# MXM_3_1_Connector_Interface.net
KiCad netlist of a schematic drawn in Altium Designer
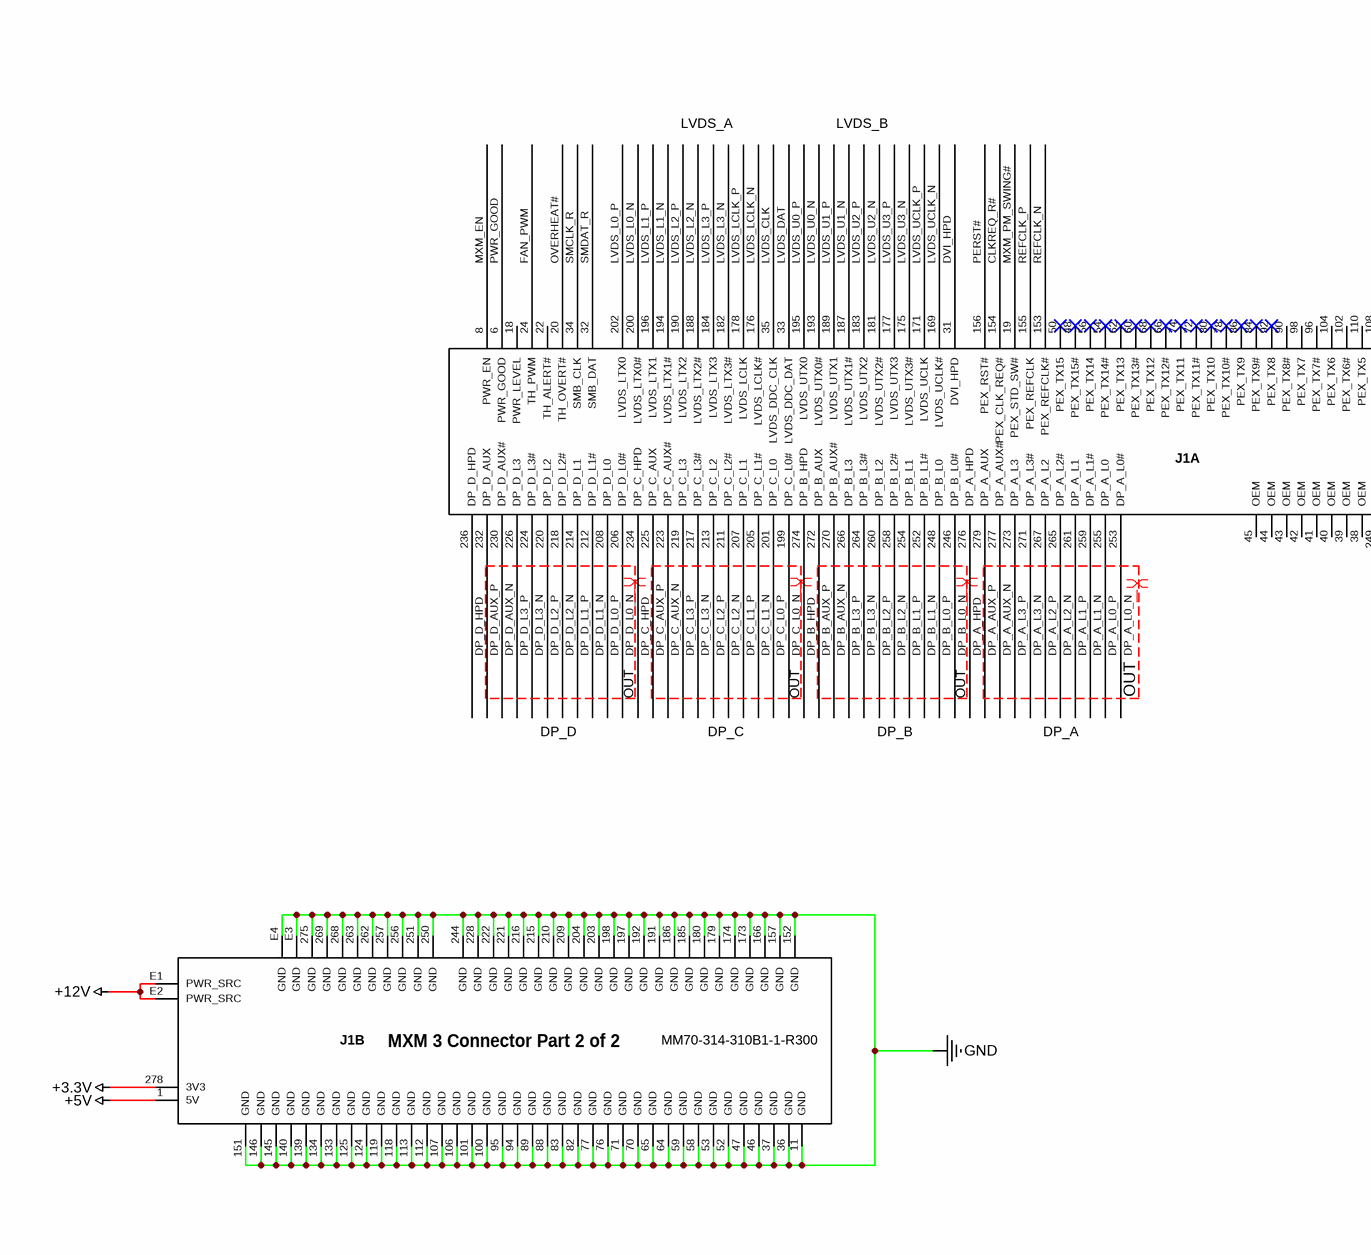
[diagram p0: MXM 3.1 Connector Interface.SchDoc, left]
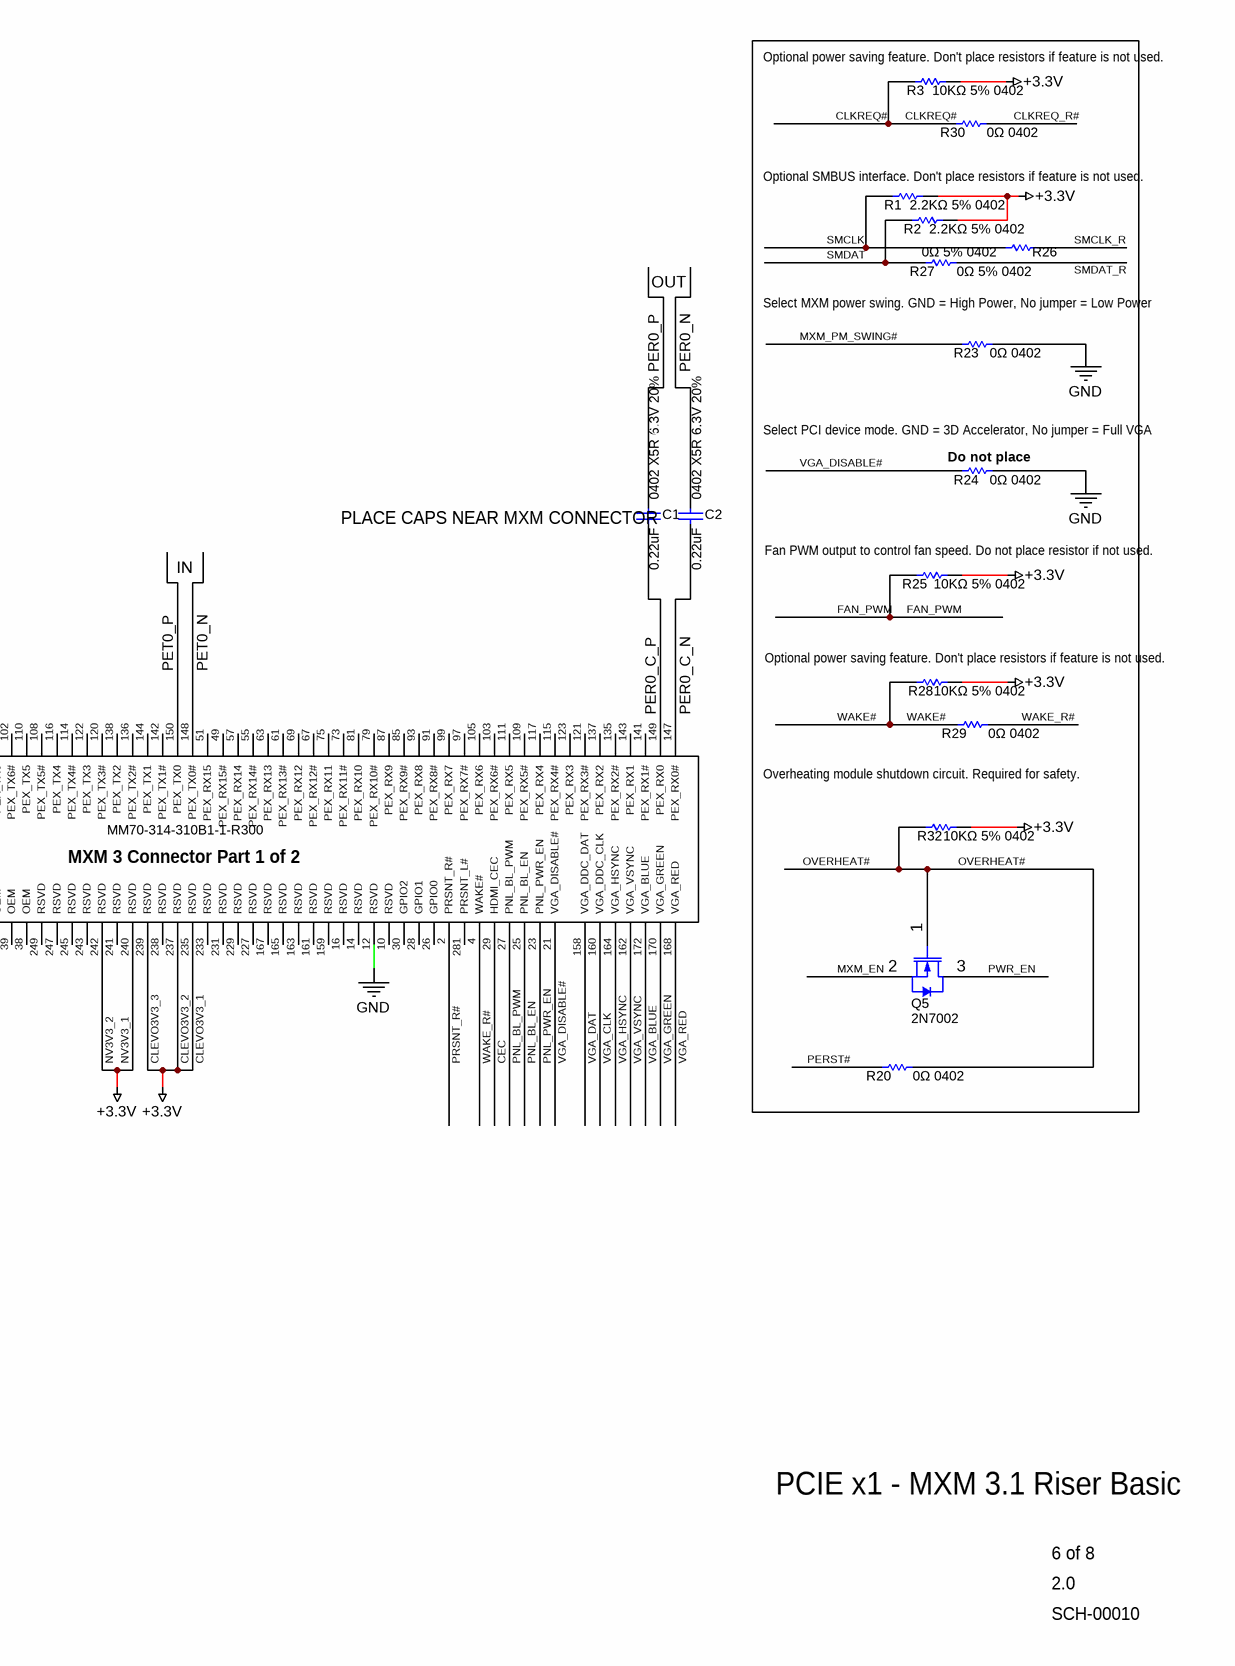
[diagram p1: MXM 3.1 Connector Interface.SchDoc, right]

(export (version "E")
  (design (tool "Eeschema 10.0.6"))
  (components
    (comp (ref "C1")
      (value "0.22uF       0402 X5R 6.3V 20%")
      (footprint "CAPC0603X33X15NL03T05")
      (fields (field (name "MANUFACTURER") "Samsung") (field (name "PART NUMBER") "CL03A224MQ3NNNC"))
      (libsource (lib "Altium Content Vault") (part "CAP"))
    )
    (comp (ref "C2")
      (value "0.22uF       0402 X5R 6.3V 20%")
      (footprint "CAPC0603X33X15NL03T05")
      (fields (field (name "MANUFACTURER") "Samsung") (field (name "PART NUMBER") "CL03A224MQ3NNNC"))
      (libsource (lib "Altium Content Vault") (part "CAP"))
    )
    (comp (ref "J1")
      (value "MM70-314-310B1-1-R300")
      (footprint "JAE_MM70-314-310B1-2-R300")
      (description "314 Position Female Connector MXM 3.0 Gold 0.020 _0.50mm_ Black")
      (fields (field (name "MF") "JAE Electronics") (field (name "DIGI-KEY_PART_NUMBER") "670-2431-1-ND"))
      (libsource (lib "MM70-314-310B1-1-R300") (part "MM70-314-310B1-1-R300"))
    )
    (comp (ref "Q5")
      (value "2N7002")
      (footprint "INF-PG-SOT23_M")
      (fields (field (name "MANUFACTURER") "Infineon"))
      (libsource (lib "Altium Content Vault") (part "INF-NDMOS-GSD-3"))
    )
    (comp (ref "R1")
      (value "2.2KΩ 5% 0402")
      (footprint "RESC0201(0603)_L")
      (description "1M 0.05W 1% 0201 (0603 Metric)  SMD")
      (fields (field (name "TOLERANCE") "1 %") (field (name "POWER") "0.05 W"))
      (libsource (lib "Altium Content Vault") (part "RES"))
    )
    (comp (ref "R2")
      (value "2.2KΩ 5% 0402")
      (footprint "RESC0201(0603)_L")
      (description "1M 0.05W 1% 0201 (0603 Metric)  SMD")
      (fields (field (name "TOLERANCE") "1 %") (field (name "POWER") "0.05 W"))
      (libsource (lib "Altium Content Vault") (part "RES"))
    )
    (comp (ref "R3")
      (value "10KΩ 5% 0402")
      (footprint "RESC0201(0603)_L")
      (description "1M 0.05W 1% 0201 (0603 Metric)  SMD")
      (fields (field (name "TOLERANCE") "1 %") (field (name "POWER") "0.05 W"))
      (libsource (lib "Altium Content Vault") (part "RES"))
    )
    (comp (ref "R20")
      (value "0Ω 0402")
      (footprint "RESC0201(0603)_L")
      (description "1M 0.05W 1% 0201 (0603 Metric)  SMD")
      (fields (field (name "TOLERANCE") "1 %") (field (name "POWER") "0.05 W"))
      (libsource (lib "Altium Content Vault") (part "RES"))
    )
    (comp (ref "R23")
      (value "0Ω 0402")
      (footprint "RESC0201(0603)_L")
      (description "1M 0.05W 1% 0201 (0603 Metric)  SMD")
      (fields (field (name "TOLERANCE") "1 %") (field (name "POWER") "0.05 W"))
      (libsource (lib "Altium Content Vault") (part "RES"))
    )
    (comp (ref "R24")
      (value "0Ω 0402")
      (footprint "RESC0201(0603)_L")
      (description "1M 0.05W 1% 0201 (0603 Metric)  SMD")
      (fields (field (name "TOLERANCE") "1 %") (field (name "POWER") "0.05 W"))
      (libsource (lib "Altium Content Vault") (part "RES"))
    )
    (comp (ref "R25")
      (value "10KΩ 5% 0402")
      (footprint "RESC0201(0603)_L")
      (description "1M 0.05W 1% 0201 (0603 Metric)  SMD")
      (fields (field (name "TOLERANCE") "1 %") (field (name "POWER") "0.05 W"))
      (libsource (lib "Altium Content Vault") (part "RES"))
    )
    (comp (ref "R26")
      (value "0Ω 5% 0402")
      (footprint "RESC0201(0603)_L")
      (description "1M 0.05W 1% 0201 (0603 Metric)  SMD")
      (fields (field (name "TOLERANCE") "1 %") (field (name "POWER") "0.05 W"))
      (libsource (lib "Altium Content Vault") (part "RES"))
    )
    (comp (ref "R27")
      (value "0Ω 5% 0402")
      (footprint "RESC0201(0603)_L")
      (description "1M 0.05W 1% 0201 (0603 Metric)  SMD")
      (fields (field (name "TOLERANCE") "1 %") (field (name "POWER") "0.05 W"))
      (libsource (lib "Altium Content Vault") (part "RES"))
    )
    (comp (ref "R28")
      (value "10KΩ 5% 0402")
      (footprint "RESC0201(0603)_L")
      (description "1M 0.05W 1% 0201 (0603 Metric)  SMD")
      (fields (field (name "TOLERANCE") "1 %") (field (name "POWER") "0.05 W"))
      (libsource (lib "Altium Content Vault") (part "RES"))
    )
    (comp (ref "R29")
      (value "0Ω 0402")
      (footprint "RESC0201(0603)_L")
      (description "1M 0.05W 1% 0201 (0603 Metric)  SMD")
      (fields (field (name "TOLERANCE") "1 %") (field (name "POWER") "0.05 W"))
      (libsource (lib "Altium Content Vault") (part "RES"))
    )
    (comp (ref "R30")
      (value "0Ω 0402")
      (footprint "RESC0201(0603)_L")
      (description "1M 0.05W 1% 0201 (0603 Metric)  SMD")
      (fields (field (name "TOLERANCE") "1 %") (field (name "POWER") "0.05 W"))
      (libsource (lib "Altium Content Vault") (part "RES"))
    )
    (comp (ref "R32")
      (value "10KΩ 5% 0402")
      (footprint "RESC0201(0603)_L")
      (description "1M 0.05W 1% 0201 (0603 Metric)  SMD")
      (fields (field (name "TOLERANCE") "1 %") (field (name "POWER") "0.05 W"))
      (libsource (lib "Altium Content Vault") (part "RES"))
    )
  )
  (nets
    (net (code "1") (name "+3.3V") (class "Default")
      (node (ref "J1") (pin "235") (pinfunction "RSVD_235") (pintype "passive"))
      (node (ref "J1") (pin "237") (pinfunction "RSVD_237") (pintype "passive"))
      (node (ref "J1") (pin "239") (pinfunction "RSVD_239") (pintype "passive"))
      (node (ref "J1") (pin "240") (pinfunction "RSVD_240") (pintype "passive"))
      (node (ref "J1") (pin "242") (pinfunction "RSVD_242") (pintype "passive"))
      (node (ref "J1") (pin "278") (pinfunction "3V3_278") (pintype "passive"))
      (node (ref "R1") (pin "1") (pinfunction "1_1") (pintype "passive"))
      (node (ref "R2") (pin "1") (pinfunction "1_1") (pintype "passive"))
      (node (ref "R25") (pin "1") (pinfunction "1_1") (pintype "passive"))
      (node (ref "R28") (pin "1") (pinfunction "1_1") (pintype "passive"))
      (node (ref "R3") (pin "1") (pinfunction "1_1") (pintype "passive"))
      (node (ref "R32") (pin "1") (pinfunction "1_1") (pintype "passive"))
    )
    (net (code "2") (name "+5V") (class "Default")
      (node (ref "J1") (pin "1") (pinfunction "5V_1") (pintype "passive"))
    )
    (net (code "3") (name "+12V") (class "Default")
      (node (ref "J1") (pin "E1") (pinfunction "PWR_SRC_E1") (pintype "passive"))
      (node (ref "J1") (pin "E2") (pinfunction "PWR_SRC_E2") (pintype "passive"))
    )
    (net (code "4") (name "/CEC") (class "Default")
      (node (ref "J1") (pin "29") (pinfunction "HDMI_CEC_29") (pintype "passive"))
    )
    (net (code "5") (name "/CLKREQ#") (class "Default")
      (node (ref "R3") (pin "2") (pinfunction "2_2") (pintype "passive"))
      (node (ref "R30") (pin "2") (pinfunction "2_2") (pintype "passive"))
    )
    (net (code "6") (name "/CLKREQ_R#") (class "Default")
      (node (ref "J1") (pin "154") (pinfunction "PEX_CLK_REQ#_154") (pintype "passive"))
      (node (ref "R30") (pin "1") (pinfunction "1_1") (pintype "passive"))
    )
    (net (code "7") (name "/DP_A_AUX_N") (class "Default")
      (node (ref "J1") (pin "277") (pinfunction "DP_A_AUX#_277") (pintype "passive"))
    )
    (net (code "8") (name "/DP_A_AUX_P") (class "Default")
      (node (ref "J1") (pin "279") (pinfunction "DP_A_AUX_279") (pintype "passive"))
    )
    (net (code "9") (name "/DP_A_HPD") (class "Default")
      (node (ref "J1") (pin "276") (pinfunction "DP_A_HPD_276") (pintype "passive"))
    )
    (net (code "10") (name "/DP_A_L0_N") (class "Default")
      (node (ref "J1") (pin "253") (pinfunction "DP_A_L0#_253") (pintype "passive"))
    )
    (net (code "11") (name "/DP_A_L0_P") (class "Default")
      (node (ref "J1") (pin "255") (pinfunction "DP_A_L0_255") (pintype "passive"))
    )
    (net (code "12") (name "/DP_A_L1_N") (class "Default")
      (node (ref "J1") (pin "259") (pinfunction "DP_A_L1#_259") (pintype "passive"))
    )
    (net (code "13") (name "/DP_A_L1_P") (class "Default")
      (node (ref "J1") (pin "261") (pinfunction "DP_A_L1_261") (pintype "passive"))
    )
    (net (code "14") (name "/DP_A_L2_N") (class "Default")
      (node (ref "J1") (pin "265") (pinfunction "DP_A_L2#_265") (pintype "passive"))
    )
    (net (code "15") (name "/DP_A_L2_P") (class "Default")
      (node (ref "J1") (pin "267") (pinfunction "DP_A_L2_267") (pintype "passive"))
    )
    (net (code "16") (name "/DP_A_L3_N") (class "Default")
      (node (ref "J1") (pin "271") (pinfunction "DP_A_L3#_271") (pintype "passive"))
    )
    (net (code "17") (name "/DP_A_L3_P") (class "Default")
      (node (ref "J1") (pin "273") (pinfunction "DP_A_L3_273") (pintype "passive"))
    )
    (net (code "18") (name "/DP_B_AUX_N") (class "Default")
      (node (ref "J1") (pin "270") (pinfunction "DP_B_AUX#_270") (pintype "passive"))
    )
    (net (code "19") (name "/DP_B_AUX_P") (class "Default")
      (node (ref "J1") (pin "272") (pinfunction "DP_B_AUX_272") (pintype "passive"))
    )
    (net (code "20") (name "/DP_B_HPD") (class "Default")
      (node (ref "J1") (pin "274") (pinfunction "DP_B_HPD_274") (pintype "passive"))
    )
    (net (code "21") (name "/DP_B_L0_N") (class "Default")
      (node (ref "J1") (pin "246") (pinfunction "DP_B_L0#_246") (pintype "passive"))
    )
    (net (code "22") (name "/DP_B_L0_P") (class "Default")
      (node (ref "J1") (pin "248") (pinfunction "DP_B_L0_248") (pintype "passive"))
    )
    (net (code "23") (name "/DP_B_L1_N") (class "Default")
      (node (ref "J1") (pin "252") (pinfunction "DP_B_L1#_252") (pintype "passive"))
    )
    (net (code "24") (name "/DP_B_L1_P") (class "Default")
      (node (ref "J1") (pin "254") (pinfunction "DP_B_L1_254") (pintype "passive"))
    )
    (net (code "25") (name "/DP_B_L2_N") (class "Default")
      (node (ref "J1") (pin "258") (pinfunction "DP_B_L2#_258") (pintype "passive"))
    )
    (net (code "26") (name "/DP_B_L2_P") (class "Default")
      (node (ref "J1") (pin "260") (pinfunction "DP_B_L2_260") (pintype "passive"))
    )
    (net (code "27") (name "/DP_B_L3_N") (class "Default")
      (node (ref "J1") (pin "264") (pinfunction "DP_B_L3#_264") (pintype "passive"))
    )
    (net (code "28") (name "/DP_B_L3_P") (class "Default")
      (node (ref "J1") (pin "266") (pinfunction "DP_B_L3_266") (pintype "passive"))
    )
    (net (code "29") (name "/DP_C_AUX_N") (class "Default")
      (node (ref "J1") (pin "223") (pinfunction "DP_C_AUX#_223") (pintype "passive"))
    )
    (net (code "30") (name "/DP_C_AUX_P") (class "Default")
      (node (ref "J1") (pin "225") (pinfunction "DP_C_AUX_225") (pintype "passive"))
    )
    (net (code "31") (name "/DP_C_HPD") (class "Default")
      (node (ref "J1") (pin "234") (pinfunction "DP_C_HPD_234") (pintype "passive"))
    )
    (net (code "32") (name "/DP_C_L0_N") (class "Default")
      (node (ref "J1") (pin "199") (pinfunction "DP_C_L0#_199") (pintype "passive"))
    )
    (net (code "33") (name "/DP_C_L0_P") (class "Default")
      (node (ref "J1") (pin "201") (pinfunction "DP_C_L0_201") (pintype "passive"))
    )
    (net (code "34") (name "/DP_C_L1_N") (class "Default")
      (node (ref "J1") (pin "205") (pinfunction "DP_C_L1#_205") (pintype "passive"))
    )
    (net (code "35") (name "/DP_C_L1_P") (class "Default")
      (node (ref "J1") (pin "207") (pinfunction "DP_C_L1_207") (pintype "passive"))
    )
    (net (code "36") (name "/DP_C_L2_N") (class "Default")
      (node (ref "J1") (pin "211") (pinfunction "DP_C_L2#_211") (pintype "passive"))
    )
    (net (code "37") (name "/DP_C_L2_P") (class "Default")
      (node (ref "J1") (pin "213") (pinfunction "DP_C_L2_213") (pintype "passive"))
    )
    (net (code "38") (name "/DP_C_L3_N") (class "Default")
      (node (ref "J1") (pin "217") (pinfunction "DP_C_L3#_217") (pintype "passive"))
    )
    (net (code "39") (name "/DP_C_L3_P") (class "Default")
      (node (ref "J1") (pin "219") (pinfunction "DP_C_L3_219") (pintype "passive"))
    )
    (net (code "40") (name "/DP_D_AUX_N") (class "Default")
      (node (ref "J1") (pin "230") (pinfunction "DP_D_AUX#_230") (pintype "passive"))
    )
    (net (code "41") (name "/DP_D_AUX_P") (class "Default")
      (node (ref "J1") (pin "232") (pinfunction "DP_D_AUX_232") (pintype "passive"))
    )
    (net (code "42") (name "/DP_D_HPD") (class "Default")
      (node (ref "J1") (pin "236") (pinfunction "DP_D_HPD_236") (pintype "passive"))
    )
    (net (code "43") (name "/DP_D_L0_N") (class "Default")
      (node (ref "J1") (pin "206") (pinfunction "DP_D_L0#_206") (pintype "passive"))
    )
    (net (code "44") (name "/DP_D_L0_P") (class "Default")
      (node (ref "J1") (pin "208") (pinfunction "DP_D_L0_208") (pintype "passive"))
    )
    (net (code "45") (name "/DP_D_L1_N") (class "Default")
      (node (ref "J1") (pin "212") (pinfunction "DP_D_L1#_212") (pintype "passive"))
    )
    (net (code "46") (name "/DP_D_L1_P") (class "Default")
      (node (ref "J1") (pin "214") (pinfunction "DP_D_L1_214") (pintype "passive"))
    )
    (net (code "47") (name "/DP_D_L2_N") (class "Default")
      (node (ref "J1") (pin "218") (pinfunction "DP_D_L2#_218") (pintype "passive"))
    )
    (net (code "48") (name "/DP_D_L2_P") (class "Default")
      (node (ref "J1") (pin "220") (pinfunction "DP_D_L2_220") (pintype "passive"))
    )
    (net (code "49") (name "/DP_D_L3_N") (class "Default")
      (node (ref "J1") (pin "224") (pinfunction "DP_D_L3#_224") (pintype "passive"))
    )
    (net (code "50") (name "/DP_D_L3_P") (class "Default")
      (node (ref "J1") (pin "226") (pinfunction "DP_D_L3_226") (pintype "passive"))
    )
    (net (code "51") (name "/DVI_HPD") (class "Default")
      (node (ref "J1") (pin "31") (pinfunction "DVI_HPD_31") (pintype "passive"))
    )
    (net (code "52") (name "/FAN_PWM") (class "Default")
      (node (ref "J1") (pin "24") (pinfunction "TH_PWM_24") (pintype "passive"))
      (node (ref "R25") (pin "2") (pinfunction "2_2") (pintype "passive"))
    )
    (net (code "53") (name "/LVDS_CLK") (class "Default")
      (node (ref "J1") (pin "35") (pinfunction "LVDS_DDC_CLK_35") (pintype "passive"))
    )
    (net (code "54") (name "/LVDS_DAT") (class "Default")
      (node (ref "J1") (pin "33") (pinfunction "LVDS_DDC_DAT_33") (pintype "passive"))
    )
    (net (code "55") (name "/LVDS_L0_N") (class "Default")
      (node (ref "J1") (pin "200") (pinfunction "LVDS_LTX0#_200") (pintype "passive"))
    )
    (net (code "56") (name "/LVDS_L0_P") (class "Default")
      (node (ref "J1") (pin "202") (pinfunction "LVDS_LTX0_202") (pintype "passive"))
    )
    (net (code "57") (name "/LVDS_L1_N") (class "Default")
      (node (ref "J1") (pin "194") (pinfunction "LVDS_LTX1#_194") (pintype "passive"))
    )
    (net (code "58") (name "/LVDS_L1_P") (class "Default")
      (node (ref "J1") (pin "196") (pinfunction "LVDS_LTX1_196") (pintype "passive"))
    )
    (net (code "59") (name "/LVDS_L2_N") (class "Default")
      (node (ref "J1") (pin "188") (pinfunction "LVDS_LTX2#_188") (pintype "passive"))
    )
    (net (code "60") (name "/LVDS_L2_P") (class "Default")
      (node (ref "J1") (pin "190") (pinfunction "LVDS_LTX2_190") (pintype "passive"))
    )
    (net (code "61") (name "/LVDS_L3_N") (class "Default")
      (node (ref "J1") (pin "182") (pinfunction "LVDS_LTX3#_182") (pintype "passive"))
    )
    (net (code "62") (name "/LVDS_L3_P") (class "Default")
      (node (ref "J1") (pin "184") (pinfunction "LVDS_LTX3_184") (pintype "passive"))
    )
    (net (code "63") (name "/LVDS_LCLK_N") (class "Default")
      (node (ref "J1") (pin "176") (pinfunction "LVDS_LCLK#_176") (pintype "passive"))
    )
    (net (code "64") (name "/LVDS_LCLK_P") (class "Default")
      (node (ref "J1") (pin "178") (pinfunction "LVDS_LCLK_178") (pintype "passive"))
    )
    (net (code "65") (name "/LVDS_U0_N") (class "Default")
      (node (ref "J1") (pin "193") (pinfunction "LVDS_UTX0#_193") (pintype "passive"))
    )
    (net (code "66") (name "/LVDS_U0_P") (class "Default")
      (node (ref "J1") (pin "195") (pinfunction "LVDS_UTX0_195") (pintype "passive"))
    )
    (net (code "67") (name "/LVDS_U1_N") (class "Default")
      (node (ref "J1") (pin "187") (pinfunction "LVDS_UTX1#_187") (pintype "passive"))
    )
    (net (code "68") (name "/LVDS_U1_P") (class "Default")
      (node (ref "J1") (pin "189") (pinfunction "LVDS_UTX1_189") (pintype "passive"))
    )
    (net (code "69") (name "/LVDS_U2_N") (class "Default")
      (node (ref "J1") (pin "181") (pinfunction "LVDS_UTX2#_181") (pintype "passive"))
    )
    (net (code "70") (name "/LVDS_U2_P") (class "Default")
      (node (ref "J1") (pin "183") (pinfunction "LVDS_UTX2_183") (pintype "passive"))
    )
    (net (code "71") (name "/LVDS_U3_N") (class "Default")
      (node (ref "J1") (pin "175") (pinfunction "LVDS_UTX3#_175") (pintype "passive"))
    )
    (net (code "72") (name "/LVDS_U3_P") (class "Default")
      (node (ref "J1") (pin "177") (pinfunction "LVDS_UTX3_177") (pintype "passive"))
    )
    (net (code "73") (name "/LVDS_UCLK_N") (class "Default")
      (node (ref "J1") (pin "169") (pinfunction "LVDS_UCLK#_169") (pintype "passive"))
    )
    (net (code "74") (name "/LVDS_UCLK_P") (class "Default")
      (node (ref "J1") (pin "171") (pinfunction "LVDS_UCLK_171") (pintype "passive"))
    )
    (net (code "75") (name "/MXM_EN") (class "Default")
      (node (ref "J1") (pin "8") (pinfunction "PWR_EN_8") (pintype "passive"))
      (node (ref "Q5") (pin "2") (pinfunction "SOURCE_2") (pintype "passive"))
    )
    (net (code "76") (name "/MXM_PM_SWING#") (class "Default")
      (node (ref "J1") (pin "19") (pinfunction "PEX_STD_SW#_19") (pintype "passive"))
      (node (ref "R23") (pin "2") (pinfunction "2_2") (pintype "passive"))
    )
    (net (code "77") (name "/OVERHEAT#") (class "Default")
      (node (ref "J1") (pin "20") (pinfunction "TH_OVERT#_20") (pintype "passive"))
      (node (ref "Q5") (pin "1") (pinfunction "GATE_1") (pintype "passive"))
      (node (ref "R20") (pin "1") (pinfunction "1_1") (pintype "passive"))
      (node (ref "R32") (pin "2") (pinfunction "2_2") (pintype "passive"))
    )
    (net (code "78") (name "/PER0_C_N") (class "Default")
      (node (ref "C2") (pin "1") (pinfunction "1_1") (pintype "passive"))
      (node (ref "J1") (pin "147") (pinfunction "PEX_RX0#_147") (pintype "passive"))
    )
    (net (code "79") (name "/PER0_C_P") (class "Default")
      (node (ref "C1") (pin "1") (pinfunction "1_1") (pintype "passive"))
      (node (ref "J1") (pin "149") (pinfunction "PEX_RX0_149") (pintype "passive"))
    )
    (net (code "80") (name "/PER0_N") (class "Default")
      (node (ref "C2") (pin "2") (pinfunction "2_2") (pintype "passive"))
    )
    (net (code "81") (name "/PER0_P") (class "Default")
      (node (ref "C1") (pin "2") (pinfunction "2_2") (pintype "passive"))
    )
    (net (code "82") (name "/PERST#") (class "Default")
      (node (ref "J1") (pin "156") (pinfunction "PEX_RST#_156") (pintype "passive"))
      (node (ref "R20") (pin "2") (pinfunction "2_2") (pintype "passive"))
    )
    (net (code "83") (name "/PET0_N") (class "Default")
      (node (ref "J1") (pin "148") (pinfunction "PEX_TX0#_148") (pintype "passive"))
    )
    (net (code "84") (name "/PET0_P") (class "Default")
      (node (ref "J1") (pin "150") (pinfunction "PEX_TX0_150") (pintype "passive"))
    )
    (net (code "85") (name "/PNL_BL_EN") (class "Default")
      (node (ref "J1") (pin "25") (pinfunction "PNL_BL_EN_25") (pintype "passive"))
    )
    (net (code "86") (name "/PNL_BL_PWM") (class "Default")
      (node (ref "J1") (pin "27") (pinfunction "PNL_BL_PWM_27") (pintype "passive"))
    )
    (net (code "87") (name "/PNL_PWR_EN") (class "Default")
      (node (ref "J1") (pin "23") (pinfunction "PNL_PWR_EN_23") (pintype "passive"))
    )
    (net (code "88") (name "/PRSNT_R#") (class "Default")
      (node (ref "J1") (pin "2") (pinfunction "PRSNT_R#_2") (pintype "passive"))
    )
    (net (code "89") (name "/PWR_EN") (class "Default")
      (node (ref "Q5") (pin "3") (pinfunction "DRAIN_3") (pintype "passive"))
    )
    (net (code "90") (name "/PWR_GOOD") (class "Default")
      (node (ref "J1") (pin "6") (pinfunction "PWR_GOOD_6") (pintype "passive"))
    )
    (net (code "91") (name "/REFCLK_N") (class "Default")
      (node (ref "J1") (pin "153") (pinfunction "PEX_REFCLK#_153") (pintype "passive"))
    )
    (net (code "92") (name "/REFCLK_P") (class "Default")
      (node (ref "J1") (pin "155") (pinfunction "PEX_REFCLK_155") (pintype "passive"))
    )
    (net (code "93") (name "/SMCLK") (class "Default")
      (node (ref "R1") (pin "2") (pinfunction "2_2") (pintype "passive"))
      (node (ref "R26") (pin "2") (pinfunction "2_2") (pintype "passive"))
    )
    (net (code "94") (name "/SMCLK_R") (class "Default")
      (node (ref "J1") (pin "34") (pinfunction "SMB_CLK_34") (pintype "passive"))
      (node (ref "R26") (pin "1") (pinfunction "1_1") (pintype "passive"))
    )
    (net (code "95") (name "/SMDAT") (class "Default")
      (node (ref "R2") (pin "2") (pinfunction "2_2") (pintype "passive"))
      (node (ref "R27") (pin "2") (pinfunction "2_2") (pintype "passive"))
    )
    (net (code "96") (name "/SMDAT_R") (class "Default")
      (node (ref "J1") (pin "32") (pinfunction "SMB_DAT_32") (pintype "passive"))
      (node (ref "R27") (pin "1") (pinfunction "1_1") (pintype "passive"))
    )
    (net (code "97") (name "/VGA_BLUE") (class "Default")
      (node (ref "J1") (pin "172") (pinfunction "VGA_BLUE_172") (pintype "passive"))
    )
    (net (code "98") (name "/VGA_CLK") (class "Default")
      (node (ref "J1") (pin "160") (pinfunction "VGA_DDC_CLK_160") (pintype "passive"))
    )
    (net (code "99") (name "/VGA_DAT") (class "Default")
      (node (ref "J1") (pin "158") (pinfunction "VGA_DDC_DAT_158") (pintype "passive"))
    )
    (net (code "100") (name "/VGA_DISABLE#") (class "Default")
      (node (ref "J1") (pin "21") (pinfunction "VGA_DISABLE#_21") (pintype "passive"))
      (node (ref "R24") (pin "2") (pinfunction "2_2") (pintype "passive"))
    )
    (net (code "101") (name "/VGA_GREEN") (class "Default")
      (node (ref "J1") (pin "170") (pinfunction "VGA_GREEN_170") (pintype "passive"))
    )
    (net (code "102") (name "/VGA_HSYNC") (class "Default")
      (node (ref "J1") (pin "164") (pinfunction "VGA_HSYNC_164") (pintype "passive"))
    )
    (net (code "103") (name "/VGA_RED") (class "Default")
      (node (ref "J1") (pin "168") (pinfunction "VGA_RED_168") (pintype "passive"))
    )
    (net (code "104") (name "/VGA_VSYNC") (class "Default")
      (node (ref "J1") (pin "162") (pinfunction "VGA_VSYNC_162") (pintype "passive"))
    )
    (net (code "105") (name "/WAKE#") (class "Default")
      (node (ref "R28") (pin "2") (pinfunction "2_2") (pintype "passive"))
      (node (ref "R29") (pin "2") (pinfunction "2_2") (pintype "passive"))
    )
    (net (code "106") (name "/WAKE_R#") (class "Default")
      (node (ref "J1") (pin "4") (pinfunction "WAKE#_4") (pintype "passive"))
      (node (ref "R29") (pin "1") (pinfunction "1_1") (pintype "passive"))
    )
    (net (code "107") (name "GND") (class "Default")
      (node (ref "J1") (pin "100") (pinfunction "GND_100") (pintype "passive"))
      (node (ref "J1") (pin "101") (pinfunction "GND_101") (pintype "passive"))
      (node (ref "J1") (pin "106") (pinfunction "GND_106") (pintype "passive"))
      (node (ref "J1") (pin "107") (pinfunction "GND_107") (pintype "passive"))
      (node (ref "J1") (pin "11") (pinfunction "GND_11") (pintype "passive"))
      (node (ref "J1") (pin "112") (pinfunction "GND_112") (pintype "passive"))
      (node (ref "J1") (pin "113") (pinfunction "GND_113") (pintype "passive"))
      (node (ref "J1") (pin "118") (pinfunction "GND_118") (pintype "passive"))
      (node (ref "J1") (pin "119") (pinfunction "GND_119") (pintype "passive"))
      (node (ref "J1") (pin "12") (pinfunction "RSVD_12") (pintype "passive"))
      (node (ref "J1") (pin "124") (pinfunction "GND_124") (pintype "passive"))
      (node (ref "J1") (pin "125") (pinfunction "GND_125") (pintype "passive"))
      (node (ref "J1") (pin "133") (pinfunction "GND_133") (pintype "passive"))
      (node (ref "J1") (pin "134") (pinfunction "GND_134") (pintype "passive"))
      (node (ref "J1") (pin "139") (pinfunction "GND_139") (pintype "passive"))
      (node (ref "J1") (pin "140") (pinfunction "GND_140") (pintype "passive"))
      (node (ref "J1") (pin "145") (pinfunction "GND_145") (pintype "passive"))
      (node (ref "J1") (pin "146") (pinfunction "GND_146") (pintype "passive"))
      (node (ref "J1") (pin "151") (pinfunction "GND_151") (pintype "passive"))
      (node (ref "J1") (pin "152") (pinfunction "GND_152") (pintype "passive"))
      (node (ref "J1") (pin "157") (pinfunction "GND_157") (pintype "passive"))
      (node (ref "J1") (pin "166") (pinfunction "GND_166") (pintype "passive"))
      (node (ref "J1") (pin "173") (pinfunction "GND_173") (pintype "passive"))
      (node (ref "J1") (pin "174") (pinfunction "GND_174") (pintype "passive"))
      (node (ref "J1") (pin "179") (pinfunction "GND_179") (pintype "passive"))
      (node (ref "J1") (pin "180") (pinfunction "GND_180") (pintype "passive"))
      (node (ref "J1") (pin "185") (pinfunction "GND_185") (pintype "passive"))
      (node (ref "J1") (pin "186") (pinfunction "GND_186") (pintype "passive"))
      (node (ref "J1") (pin "191") (pinfunction "GND_191") (pintype "passive"))
      (node (ref "J1") (pin "192") (pinfunction "GND_192") (pintype "passive"))
      (node (ref "J1") (pin "197") (pinfunction "GND_197") (pintype "passive"))
      (node (ref "J1") (pin "198") (pinfunction "GND_198") (pintype "passive"))
      (node (ref "J1") (pin "203") (pinfunction "GND_203") (pintype "passive"))
      (node (ref "J1") (pin "204") (pinfunction "GND_204") (pintype "passive"))
      (node (ref "J1") (pin "209") (pinfunction "GND_209") (pintype "passive"))
      (node (ref "J1") (pin "210") (pinfunction "GND_210") (pintype "passive"))
      (node (ref "J1") (pin "215") (pinfunction "GND_215") (pintype "passive"))
      (node (ref "J1") (pin "216") (pinfunction "GND_216") (pintype "passive"))
      (node (ref "J1") (pin "221") (pinfunction "GND_221") (pintype "passive"))
      (node (ref "J1") (pin "222") (pinfunction "GND_222") (pintype "passive"))
      (node (ref "J1") (pin "228") (pinfunction "GND_228") (pintype "passive"))
      (node (ref "J1") (pin "244") (pinfunction "GND_244") (pintype "passive"))
      (node (ref "J1") (pin "250") (pinfunction "GND_250") (pintype "passive"))
      (node (ref "J1") (pin "251") (pinfunction "GND_251") (pintype "passive"))
      (node (ref "J1") (pin "256") (pinfunction "GND_256") (pintype "passive"))
      (node (ref "J1") (pin "257") (pinfunction "GND_257") (pintype "passive"))
      (node (ref "J1") (pin "262") (pinfunction "GND_262") (pintype "passive"))
      (node (ref "J1") (pin "263") (pinfunction "GND_263") (pintype "passive"))
      (node (ref "J1") (pin "268") (pinfunction "GND_268") (pintype "passive"))
      (node (ref "J1") (pin "269") (pinfunction "GND_269") (pintype "passive"))
      (node (ref "J1") (pin "275") (pinfunction "GND_275") (pintype "passive"))
      (node (ref "J1") (pin "36") (pinfunction "GND_36") (pintype "passive"))
      (node (ref "J1") (pin "37") (pinfunction "GND_37") (pintype "passive"))
      (node (ref "J1") (pin "46") (pinfunction "GND_46") (pintype "passive"))
      (node (ref "J1") (pin "47") (pinfunction "GND_47") (pintype "passive"))
      (node (ref "J1") (pin "52") (pinfunction "GND_52") (pintype "passive"))
      (node (ref "J1") (pin "53") (pinfunction "GND_53") (pintype "passive"))
      (node (ref "J1") (pin "58") (pinfunction "GND_58") (pintype "passive"))
      (node (ref "J1") (pin "59") (pinfunction "GND_59") (pintype "passive"))
      (node (ref "J1") (pin "64") (pinfunction "GND_64") (pintype "passive"))
      (node (ref "J1") (pin "65") (pinfunction "GND_65") (pintype "passive"))
      (node (ref "J1") (pin "70") (pinfunction "GND_70") (pintype "passive"))
      (node (ref "J1") (pin "71") (pinfunction "GND_71") (pintype "passive"))
      (node (ref "J1") (pin "76") (pinfunction "GND_76") (pintype "passive"))
      (node (ref "J1") (pin "77") (pinfunction "GND_77") (pintype "passive"))
      (node (ref "J1") (pin "82") (pinfunction "GND_82") (pintype "passive"))
      (node (ref "J1") (pin "83") (pinfunction "GND_83") (pintype "passive"))
      (node (ref "J1") (pin "88") (pinfunction "GND_88") (pintype "passive"))
      (node (ref "J1") (pin "89") (pinfunction "GND_89") (pintype "passive"))
      (node (ref "J1") (pin "94") (pinfunction "GND_94") (pintype "passive"))
      (node (ref "J1") (pin "95") (pinfunction "GND_95") (pintype "passive"))
      (node (ref "J1") (pin "E3") (pinfunction "GND_E3") (pintype "passive"))
      (node (ref "J1") (pin "E4") (pinfunction "GND_E4") (pintype "passive"))
      (node (ref "R23") (pin "1") (pinfunction "1_1") (pintype "passive"))
      (node (ref "R24") (pin "1") (pinfunction "1_1") (pintype "passive"))
    )
    (net (code "108") (name "unconnected-(J1A-GPIO0-Pad26)") (class "Default")
      (node (ref "J1") (pin "26") (pinfunction "GPIO0_26") (pintype "passive"))
    )
    (net (code "109") (name "unconnected-(J1A-GPIO1-Pad28)") (class "Default")
      (node (ref "J1") (pin "28") (pinfunction "GPIO1_28") (pintype "passive"))
    )
    (net (code "110") (name "unconnected-(J1A-GPIO2-Pad30)") (class "Default")
      (node (ref "J1") (pin "30") (pinfunction "GPIO2_30") (pintype "passive"))
    )
    (net (code "111") (name "unconnected-(J1A-OEM-Pad38)") (class "Default")
      (node (ref "J1") (pin "38") (pinfunction "OEM_38") (pintype "passive"))
    )
    (net (code "112") (name "unconnected-(J1A-OEM-Pad39)") (class "Default")
      (node (ref "J1") (pin "39") (pinfunction "OEM_39") (pintype "passive"))
    )
    (net (code "113") (name "unconnected-(J1A-OEM-Pad40)") (class "Default")
      (node (ref "J1") (pin "40") (pinfunction "OEM_40") (pintype "passive"))
    )
    (net (code "114") (name "unconnected-(J1A-OEM-Pad41)") (class "Default")
      (node (ref "J1") (pin "41") (pinfunction "OEM_41") (pintype "passive"))
    )
    (net (code "115") (name "unconnected-(J1A-OEM-Pad42)") (class "Default")
      (node (ref "J1") (pin "42") (pinfunction "OEM_42") (pintype "passive"))
    )
    (net (code "116") (name "unconnected-(J1A-OEM-Pad43)") (class "Default")
      (node (ref "J1") (pin "43") (pinfunction "OEM_43") (pintype "passive"))
    )
    (net (code "117") (name "unconnected-(J1A-OEM-Pad44)") (class "Default")
      (node (ref "J1") (pin "44") (pinfunction "OEM_44") (pintype "passive"))
    )
    (net (code "118") (name "unconnected-(J1A-OEM-Pad45)") (class "Default")
      (node (ref "J1") (pin "45") (pinfunction "OEM_45") (pintype "passive"))
    )
    (net (code "119") (name "unconnected-(J1A-PEX_RX1#-Pad141)") (class "Default")
      (node (ref "J1") (pin "141") (pinfunction "PEX_RX1#_141") (pintype "passive"))
    )
    (net (code "120") (name "unconnected-(J1A-PEX_RX1-Pad143)") (class "Default")
      (node (ref "J1") (pin "143") (pinfunction "PEX_RX1_143") (pintype "passive"))
    )
    (net (code "121") (name "unconnected-(J1A-PEX_RX2#-Pad135)") (class "Default")
      (node (ref "J1") (pin "135") (pinfunction "PEX_RX2#_135") (pintype "passive"))
    )
    (net (code "122") (name "unconnected-(J1A-PEX_RX2-Pad137)") (class "Default")
      (node (ref "J1") (pin "137") (pinfunction "PEX_RX2_137") (pintype "passive"))
    )
    (net (code "123") (name "unconnected-(J1A-PEX_RX3#-Pad121)") (class "Default")
      (node (ref "J1") (pin "121") (pinfunction "PEX_RX3#_121") (pintype "passive"))
    )
    (net (code "124") (name "unconnected-(J1A-PEX_RX3-Pad123)") (class "Default")
      (node (ref "J1") (pin "123") (pinfunction "PEX_RX3_123") (pintype "passive"))
    )
    (net (code "125") (name "unconnected-(J1A-PEX_RX4#-Pad115)") (class "Default")
      (node (ref "J1") (pin "115") (pinfunction "PEX_RX4#_115") (pintype "passive"))
    )
    (net (code "126") (name "unconnected-(J1A-PEX_RX4-Pad117)") (class "Default")
      (node (ref "J1") (pin "117") (pinfunction "PEX_RX4_117") (pintype "passive"))
    )
    (net (code "127") (name "unconnected-(J1A-PEX_RX5#-Pad109)") (class "Default")
      (node (ref "J1") (pin "109") (pinfunction "PEX_RX5#_109") (pintype "passive"))
    )
    (net (code "128") (name "unconnected-(J1A-PEX_RX5-Pad111)") (class "Default")
      (node (ref "J1") (pin "111") (pinfunction "PEX_RX5_111") (pintype "passive"))
    )
    (net (code "129") (name "unconnected-(J1A-PEX_RX6#-Pad103)") (class "Default")
      (node (ref "J1") (pin "103") (pinfunction "PEX_RX6#_103") (pintype "passive"))
    )
    (net (code "130") (name "unconnected-(J1A-PEX_RX6-Pad105)") (class "Default")
      (node (ref "J1") (pin "105") (pinfunction "PEX_RX6_105") (pintype "passive"))
    )
    (net (code "131") (name "unconnected-(J1A-PEX_RX7#-Pad97)") (class "Default")
      (node (ref "J1") (pin "97") (pinfunction "PEX_RX7#_97") (pintype "passive"))
    )
    (net (code "132") (name "unconnected-(J1A-PEX_RX7-Pad99)") (class "Default")
      (node (ref "J1") (pin "99") (pinfunction "PEX_RX7_99") (pintype "passive"))
    )
    (net (code "133") (name "unconnected-(J1A-PEX_RX8#-Pad91)") (class "Default")
      (node (ref "J1") (pin "91") (pinfunction "PEX_RX8#_91") (pintype "passive"))
    )
    (net (code "134") (name "unconnected-(J1A-PEX_RX8-Pad93)") (class "Default")
      (node (ref "J1") (pin "93") (pinfunction "PEX_RX8_93") (pintype "passive"))
    )
    (net (code "135") (name "unconnected-(J1A-PEX_RX9#-Pad85)") (class "Default")
      (node (ref "J1") (pin "85") (pinfunction "PEX_RX9#_85") (pintype "passive"))
    )
    (net (code "136") (name "unconnected-(J1A-PEX_RX9-Pad87)") (class "Default")
      (node (ref "J1") (pin "87") (pinfunction "PEX_RX9_87") (pintype "passive"))
    )
    (net (code "137") (name "unconnected-(J1A-PEX_RX10#-Pad79)") (class "Default")
      (node (ref "J1") (pin "79") (pinfunction "PEX_RX10#_79") (pintype "passive"))
    )
    (net (code "138") (name "unconnected-(J1A-PEX_RX10-Pad81)") (class "Default")
      (node (ref "J1") (pin "81") (pinfunction "PEX_RX10_81") (pintype "passive"))
    )
    (net (code "139") (name "unconnected-(J1A-PEX_RX11#-Pad73)") (class "Default")
      (node (ref "J1") (pin "73") (pinfunction "PEX_RX11#_73") (pintype "passive"))
    )
    (net (code "140") (name "unconnected-(J1A-PEX_RX11-Pad75)") (class "Default")
      (node (ref "J1") (pin "75") (pinfunction "PEX_RX11_75") (pintype "passive"))
    )
    (net (code "141") (name "unconnected-(J1A-PEX_RX12#-Pad67)") (class "Default")
      (node (ref "J1") (pin "67") (pinfunction "PEX_RX12#_67") (pintype "passive"))
    )
    (net (code "142") (name "unconnected-(J1A-PEX_RX12-Pad69)") (class "Default")
      (node (ref "J1") (pin "69") (pinfunction "PEX_RX12_69") (pintype "passive"))
    )
    (net (code "143") (name "unconnected-(J1A-PEX_RX13#-Pad61)") (class "Default")
      (node (ref "J1") (pin "61") (pinfunction "PEX_RX13#_61") (pintype "passive"))
    )
    (net (code "144") (name "unconnected-(J1A-PEX_RX13-Pad63)") (class "Default")
      (node (ref "J1") (pin "63") (pinfunction "PEX_RX13_63") (pintype "passive"))
    )
    (net (code "145") (name "unconnected-(J1A-PEX_RX14#-Pad55)") (class "Default")
      (node (ref "J1") (pin "55") (pinfunction "PEX_RX14#_55") (pintype "passive"))
    )
    (net (code "146") (name "unconnected-(J1A-PEX_RX14-Pad57)") (class "Default")
      (node (ref "J1") (pin "57") (pinfunction "PEX_RX14_57") (pintype "passive"))
    )
    (net (code "147") (name "unconnected-(J1A-PEX_RX15#-Pad49)") (class "Default")
      (node (ref "J1") (pin "49") (pinfunction "PEX_RX15#_49") (pintype "passive"))
    )
    (net (code "148") (name "unconnected-(J1A-PEX_RX15-Pad51)") (class "Default")
      (node (ref "J1") (pin "51") (pinfunction "PEX_RX15_51") (pintype "passive"))
    )
    (net (code "149") (name "unconnected-(J1A-PEX_TX1#-Pad142)") (class "Default")
      (node (ref "J1") (pin "142") (pinfunction "PEX_TX1#_142") (pintype "passive"))
    )
    (net (code "150") (name "unconnected-(J1A-PEX_TX1-Pad144)") (class "Default")
      (node (ref "J1") (pin "144") (pinfunction "PEX_TX1_144") (pintype "passive"))
    )
    (net (code "151") (name "unconnected-(J1A-PEX_TX2#-Pad136)") (class "Default")
      (node (ref "J1") (pin "136") (pinfunction "PEX_TX2#_136") (pintype "passive"))
    )
    (net (code "152") (name "unconnected-(J1A-PEX_TX2-Pad138)") (class "Default")
      (node (ref "J1") (pin "138") (pinfunction "PEX_TX2_138") (pintype "passive"))
    )
    (net (code "153") (name "unconnected-(J1A-PEX_TX3#-Pad120)") (class "Default")
      (node (ref "J1") (pin "120") (pinfunction "PEX_TX3#_120") (pintype "passive"))
    )
    (net (code "154") (name "unconnected-(J1A-PEX_TX3-Pad122)") (class "Default")
      (node (ref "J1") (pin "122") (pinfunction "PEX_TX3_122") (pintype "passive"))
    )
    (net (code "155") (name "unconnected-(J1A-PEX_TX4#-Pad114)") (class "Default")
      (node (ref "J1") (pin "114") (pinfunction "PEX_TX4#_114") (pintype "passive"))
    )
    (net (code "156") (name "unconnected-(J1A-PEX_TX4-Pad116)") (class "Default")
      (node (ref "J1") (pin "116") (pinfunction "PEX_TX4_116") (pintype "passive"))
    )
    (net (code "157") (name "unconnected-(J1A-PEX_TX5#-Pad108)") (class "Default")
      (node (ref "J1") (pin "108") (pinfunction "PEX_TX5#_108") (pintype "passive"))
    )
    (net (code "158") (name "unconnected-(J1A-PEX_TX5-Pad110)") (class "Default")
      (node (ref "J1") (pin "110") (pinfunction "PEX_TX5_110") (pintype "passive"))
    )
    (net (code "159") (name "unconnected-(J1A-PEX_TX6#-Pad102)") (class "Default")
      (node (ref "J1") (pin "102") (pinfunction "PEX_TX6#_102") (pintype "passive"))
    )
    (net (code "160") (name "unconnected-(J1A-PEX_TX6-Pad104)") (class "Default")
      (node (ref "J1") (pin "104") (pinfunction "PEX_TX6_104") (pintype "passive"))
    )
    (net (code "161") (name "unconnected-(J1A-PEX_TX7#-Pad96)") (class "Default")
      (node (ref "J1") (pin "96") (pinfunction "PEX_TX7#_96") (pintype "passive"))
    )
    (net (code "162") (name "unconnected-(J1A-PEX_TX7-Pad98)") (class "Default")
      (node (ref "J1") (pin "98") (pinfunction "PEX_TX7_98") (pintype "passive"))
    )
    (net (code "163") (name "unconnected-(J1A-PEX_TX8#-Pad90)") (class "Default")
      (node (ref "J1") (pin "90") (pinfunction "PEX_TX8#_90") (pintype "passive"))
    )
    (net (code "164") (name "unconnected-(J1A-PEX_TX8-Pad92)") (class "Default")
      (node (ref "J1") (pin "92") (pinfunction "PEX_TX8_92") (pintype "passive+no_connect"))
    )
    (net (code "165") (name "unconnected-(J1A-PEX_TX9#-Pad84)") (class "Default")
      (node (ref "J1") (pin "84") (pinfunction "PEX_TX9#_84") (pintype "passive+no_connect"))
    )
    (net (code "166") (name "unconnected-(J1A-PEX_TX9-Pad86)") (class "Default")
      (node (ref "J1") (pin "86") (pinfunction "PEX_TX9_86") (pintype "passive+no_connect"))
    )
    (net (code "167") (name "unconnected-(J1A-PEX_TX10#-Pad78)") (class "Default")
      (node (ref "J1") (pin "78") (pinfunction "PEX_TX10#_78") (pintype "passive+no_connect"))
    )
    (net (code "168") (name "unconnected-(J1A-PEX_TX10-Pad80)") (class "Default")
      (node (ref "J1") (pin "80") (pinfunction "PEX_TX10_80") (pintype "passive+no_connect"))
    )
    (net (code "169") (name "unconnected-(J1A-PEX_TX11#-Pad72)") (class "Default")
      (node (ref "J1") (pin "72") (pinfunction "PEX_TX11#_72") (pintype "passive+no_connect"))
    )
    (net (code "170") (name "unconnected-(J1A-PEX_TX11-Pad74)") (class "Default")
      (node (ref "J1") (pin "74") (pinfunction "PEX_TX11_74") (pintype "passive+no_connect"))
    )
    (net (code "171") (name "unconnected-(J1A-PEX_TX12#-Pad66)") (class "Default")
      (node (ref "J1") (pin "66") (pinfunction "PEX_TX12#_66") (pintype "passive+no_connect"))
    )
    (net (code "172") (name "unconnected-(J1A-PEX_TX12-Pad68)") (class "Default")
      (node (ref "J1") (pin "68") (pinfunction "PEX_TX12_68") (pintype "passive+no_connect"))
    )
    (net (code "173") (name "unconnected-(J1A-PEX_TX13#-Pad60)") (class "Default")
      (node (ref "J1") (pin "60") (pinfunction "PEX_TX13#_60") (pintype "passive+no_connect"))
    )
    (net (code "174") (name "unconnected-(J1A-PEX_TX13-Pad62)") (class "Default")
      (node (ref "J1") (pin "62") (pinfunction "PEX_TX13_62") (pintype "passive+no_connect"))
    )
    (net (code "175") (name "unconnected-(J1A-PEX_TX14#-Pad54)") (class "Default")
      (node (ref "J1") (pin "54") (pinfunction "PEX_TX14#_54") (pintype "passive+no_connect"))
    )
    (net (code "176") (name "unconnected-(J1A-PEX_TX14-Pad56)") (class "Default")
      (node (ref "J1") (pin "56") (pinfunction "PEX_TX14_56") (pintype "passive+no_connect"))
    )
    (net (code "177") (name "unconnected-(J1A-PEX_TX15#-Pad48)") (class "Default")
      (node (ref "J1") (pin "48") (pinfunction "PEX_TX15#_48") (pintype "passive+no_connect"))
    )
    (net (code "178") (name "unconnected-(J1A-PEX_TX15-Pad50)") (class "Default")
      (node (ref "J1") (pin "50") (pinfunction "PEX_TX15_50") (pintype "passive+no_connect"))
    )
    (net (code "179") (name "unconnected-(J1A-PRSNT_L#-Pad281)") (class "Default")
      (node (ref "J1") (pin "281") (pinfunction "PRSNT_L#_281") (pintype "passive"))
    )
    (net (code "180") (name "unconnected-(J1A-PWR_LEVEL-Pad18)") (class "Default")
      (node (ref "J1") (pin "18") (pinfunction "PWR_LEVEL_18") (pintype "passive"))
    )
    (net (code "181") (name "unconnected-(J1A-RSVD-Pad10)") (class "Default")
      (node (ref "J1") (pin "10") (pinfunction "RSVD_10") (pintype "passive"))
    )
    (net (code "182") (name "unconnected-(J1A-RSVD-Pad14)") (class "Default")
      (node (ref "J1") (pin "14") (pinfunction "RSVD_14") (pintype "passive"))
    )
    (net (code "183") (name "unconnected-(J1A-RSVD-Pad16)") (class "Default")
      (node (ref "J1") (pin "16") (pinfunction "RSVD_16") (pintype "passive"))
    )
    (net (code "184") (name "unconnected-(J1A-RSVD-Pad159)") (class "Default")
      (node (ref "J1") (pin "159") (pinfunction "RSVD_159") (pintype "passive"))
    )
    (net (code "185") (name "unconnected-(J1A-RSVD-Pad161)") (class "Default")
      (node (ref "J1") (pin "161") (pinfunction "RSVD_161") (pintype "passive"))
    )
    (net (code "186") (name "unconnected-(J1A-RSVD-Pad163)") (class "Default")
      (node (ref "J1") (pin "163") (pinfunction "RSVD_163") (pintype "passive"))
    )
    (net (code "187") (name "unconnected-(J1A-RSVD-Pad165)") (class "Default")
      (node (ref "J1") (pin "165") (pinfunction "RSVD_165") (pintype "passive"))
    )
    (net (code "188") (name "unconnected-(J1A-RSVD-Pad167)") (class "Default")
      (node (ref "J1") (pin "167") (pinfunction "RSVD_167") (pintype "passive"))
    )
    (net (code "189") (name "unconnected-(J1A-RSVD-Pad227)") (class "Default")
      (node (ref "J1") (pin "227") (pinfunction "RSVD_227") (pintype "passive"))
    )
    (net (code "190") (name "unconnected-(J1A-RSVD-Pad229)") (class "Default")
      (node (ref "J1") (pin "229") (pinfunction "RSVD_229") (pintype "passive"))
    )
    (net (code "191") (name "unconnected-(J1A-RSVD-Pad231)") (class "Default")
      (node (ref "J1") (pin "231") (pinfunction "RSVD_231") (pintype "passive"))
    )
    (net (code "192") (name "unconnected-(J1A-RSVD-Pad233)") (class "Default")
      (node (ref "J1") (pin "233") (pinfunction "RSVD_233") (pintype "passive"))
    )
    (net (code "193") (name "unconnected-(J1A-RSVD-Pad238)") (class "Default")
      (node (ref "J1") (pin "238") (pinfunction "RSVD_238") (pintype "passive"))
    )
    (net (code "194") (name "unconnected-(J1A-RSVD-Pad241)") (class "Default")
      (node (ref "J1") (pin "241") (pinfunction "RSVD_241") (pintype "passive"))
    )
    (net (code "195") (name "unconnected-(J1A-RSVD-Pad243)") (class "Default")
      (node (ref "J1") (pin "243") (pinfunction "RSVD_243") (pintype "passive"))
    )
    (net (code "196") (name "unconnected-(J1A-RSVD-Pad245)") (class "Default")
      (node (ref "J1") (pin "245") (pinfunction "RSVD_245") (pintype "passive"))
    )
    (net (code "197") (name "unconnected-(J1A-RSVD-Pad247)") (class "Default")
      (node (ref "J1") (pin "247") (pinfunction "RSVD_247") (pintype "passive"))
    )
    (net (code "198") (name "unconnected-(J1A-RSVD-Pad249)") (class "Default")
      (node (ref "J1") (pin "249") (pinfunction "RSVD_249") (pintype "passive"))
    )
    (net (code "199") (name "unconnected-(J1A-TH_ALERT#-Pad22)") (class "Default")
      (node (ref "J1") (pin "22") (pinfunction "TH_ALERT#_22") (pintype "passive"))
    )
  )
)
